# OnOnfre_DevBoard.net
KiCad netlist of a schematic drawn in EAGLE
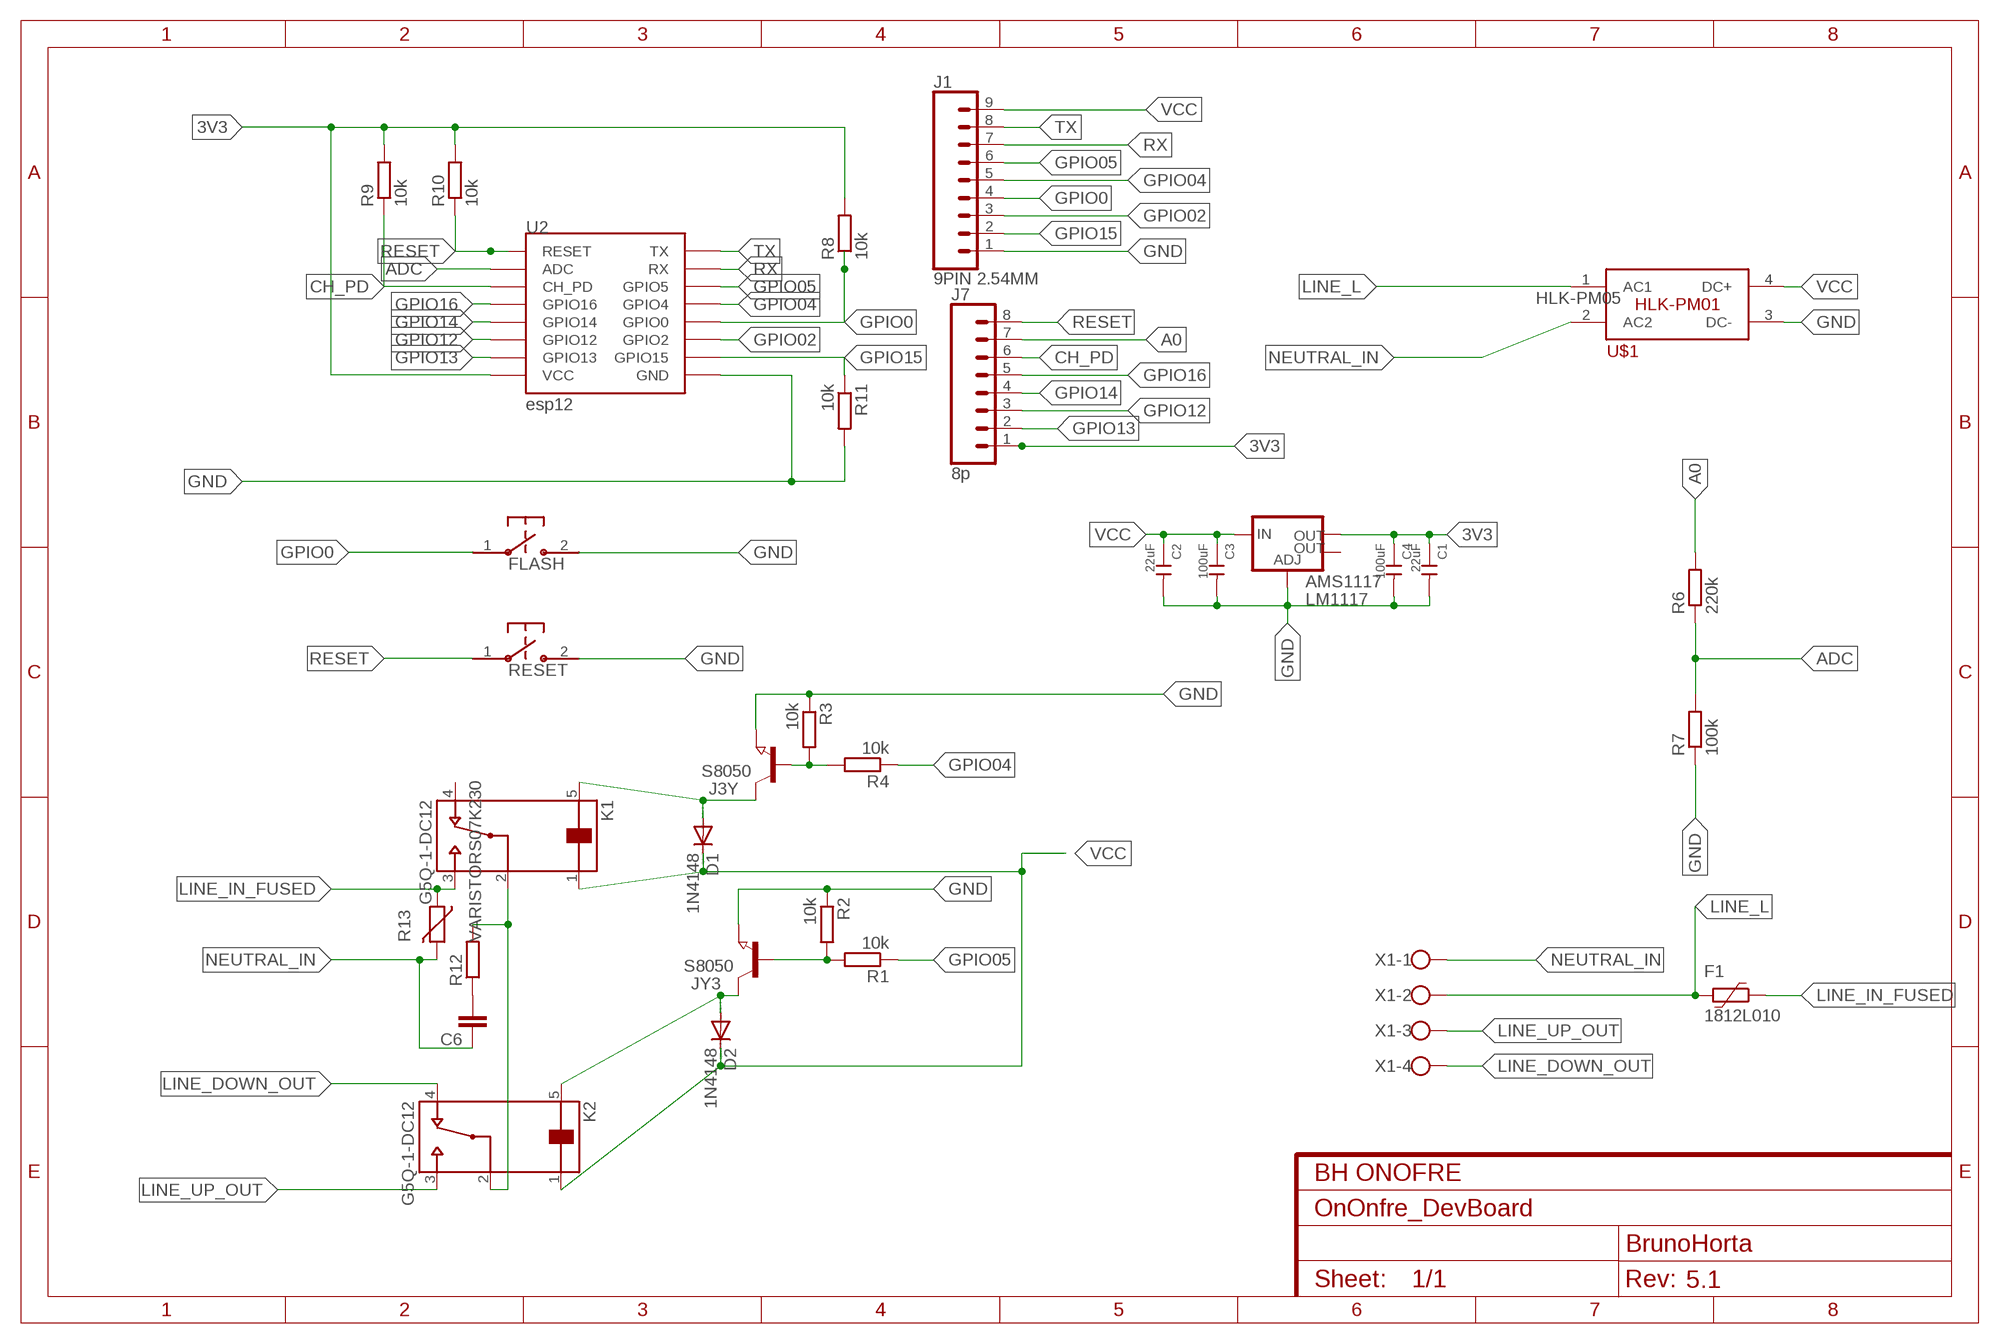
[diagram p0: schematic, sheet 1]

(export (version "E")
  (design (tool "Eeschema 10.0.6"))
  (components
    (comp (ref "AMS1117")
      (value "LM1117")
      (footprint "eagle-import:SOT223")
      (libsource (lib "eagle-import") (part "V_REG_LM1117SOT223"))
    )
    (comp (ref "C1")
      (value "22uF")
      (footprint "eagle-import:C1206")
      (fields (field (name "MPN") "CC1206KKX7RCBB102"))
      (libsource (lib "eagle-import") (part "CERAMIC-1NF-1KV-10%-X7R?(1206)"))
    )
    (comp (ref "C2")
      (value "22uF")
      (footprint "eagle-import:C1206")
      (fields (field (name "MPN") "CC1206KKX7RCBB102"))
      (libsource (lib "eagle-import") (part "CERAMIC-1NF-1KV-10%-X7R?(1206)"))
    )
    (comp (ref "C3")
      (value "100uF")
      (footprint "eagle-import:C1206")
      (fields (field (name "MPN") "CC1206KKX7RCBB102"))
      (libsource (lib "eagle-import") (part "CERAMIC-1NF-1KV-10%-X7R?(1206)"))
    )
    (comp (ref "C4")
      (value "100uF")
      (footprint "eagle-import:C1206")
      (fields (field (name "MPN") "CC1206KKX7RCBB102"))
      (libsource (lib "eagle-import") (part "CERAMIC-1NF-1KV-10%-X7R?(1206)"))
    )
    (comp (ref "C6")
      (value "C-EU102-043X133")
      (footprint "eagle-import:C102-043X133")
      (libsource (lib "eagle-import") (part "C-EU102-043X133"))
    )
    (comp (ref "D1")
      (value "1N4148")
      (footprint "eagle-import:SOD80C")
      (libsource (lib "eagle-import") (part "DIODE-SOD80C"))
    )
    (comp (ref "D2")
      (value "1N4148")
      (footprint "eagle-import:SOD80C")
      (libsource (lib "eagle-import") (part "DIODE-SOD80C"))
    )
    (comp (ref "F1")
      (value "1812L010")
      (footprint "eagle-import:1812L")
      (fields (field (name "MF") "Littelfuse"))
      (libsource (lib "eagle-import") (part "?1812L010"))
    )
    (comp (ref "FLASH")
      (value "B3U-1000P-2P-SMD")
      (footprint "eagle-import:B3U-1000P")
      (fields (field (name "MANUFACTURER") "Omron") (field (name "MPN") "B3U-1000P"))
      (libsource (lib "eagle-import") (part "B3U-1000P"))
    )
    (comp (ref "J1")
      (value "9PIN 2.54MM")
      (footprint "eagle-import:1X09")
      (libsource (lib "eagle-import") (part "CONN_09"))
    )
    (comp (ref "J3Y")
      (value "S8050")
      (footprint "eagle-import:SOT23")
      (libsource (lib "eagle-import") (part "NPN-TRANSISTOR_SOT23"))
    )
    (comp (ref "J7")
      (value "8p")
      (footprint "eagle-import:1X08")
      (libsource (lib "eagle-import") (part "CONN_08{dblquote}"))
    )
    (comp (ref "JY3")
      (value "S8050")
      (footprint "eagle-import:SOT23")
      (libsource (lib "eagle-import") (part "NPN-TRANSISTOR_SOT23"))
    )
    (comp (ref "K1")
      (value "G5Q-1-DC12")
      (footprint "eagle-import:RELAY_G5Q-1-DC12")
      (fields (field (name "MF") "Omron"))
      (libsource (lib "eagle-import") (part "G5Q-1-DC12"))
    )
    (comp (ref "K2")
      (value "G5Q-1-DC12")
      (footprint "eagle-import:RELAY_G5Q-1-DC12")
      (fields (field (name "MF") "Omron"))
      (libsource (lib "eagle-import") (part "G5Q-1-DC12"))
    )
    (comp (ref "R1")
      (value "10k")
      (footprint "eagle-import:R0603")
      (libsource (lib "eagle-import") (part "R-EU_R0603"))
    )
    (comp (ref "R2")
      (value "10k")
      (footprint "eagle-import:R0603")
      (libsource (lib "eagle-import") (part "R-EU_R0603"))
    )
    (comp (ref "R3")
      (value "10k")
      (footprint "eagle-import:R0603")
      (libsource (lib "eagle-import") (part "R-EU_R0603"))
    )
    (comp (ref "R4")
      (value "10k")
      (footprint "eagle-import:R0603")
      (libsource (lib "eagle-import") (part "R-EU_R0603"))
    )
    (comp (ref "R6")
      (value "220k")
      (footprint "eagle-import:R0603")
      (libsource (lib "eagle-import") (part "R-EU_R0603"))
    )
    (comp (ref "R7")
      (value "100k")
      (footprint "eagle-import:R0603")
      (libsource (lib "eagle-import") (part "R-EU_R0603"))
    )
    (comp (ref "R8")
      (value "10k")
      (footprint "eagle-import:R0603")
      (libsource (lib "eagle-import") (part "R-EU_R0603"))
    )
    (comp (ref "R9")
      (value "10k")
      (footprint "eagle-import:R0603")
      (libsource (lib "eagle-import") (part "R-EU_R0603"))
    )
    (comp (ref "R10")
      (value "10k")
      (footprint "eagle-import:R0603")
      (libsource (lib "eagle-import") (part "R-EU_R0603"))
    )
    (comp (ref "R11")
      (value "10k")
      (footprint "eagle-import:R0603")
      (libsource (lib "eagle-import") (part "R-EU_R0603"))
    )
    (comp (ref "R12")
      (value "R-EU_R2512")
      (footprint "eagle-import:R2512")
      (libsource (lib "eagle-import") (part "R-EU_R2512"))
    )
    (comp (ref "R13")
      (value "VARISTORS07K230")
      (footprint "eagle-import:S07K230")
      (libsource (lib "eagle-import") (part "VARISTORS07K230"))
    )
    (comp (ref "RESET")
      (value "B3U-1000P-2P-SMD")
      (footprint "eagle-import:B3U-1000P")
      (fields (field (name "MANUFACTURER") "Omron") (field (name "MPN") "B3U-1000P"))
      (libsource (lib "eagle-import") (part "B3U-1000P"))
    )
    (comp (ref "U$1")
      (value "HLK-PM01")
      (footprint "eagle-import:HLK-PM01")
      (fields (field (name "MF") "Hi-link") (field (name "MP") "hlk-pm01"))
      (libsource (lib "eagle-import") (part "HLK-PM01"))
    )
    (comp (ref "U2")
      (value "esp12")
      (footprint "eagle-import:ESP12-SMD")
      (libsource (lib "eagle-import") (part "ESP12SMD"))
    )
    (comp (ref "X1")
      (value "W237-4")
      (footprint "eagle-import:W237-4")
      (libsource (lib "eagle-import") (part "W237-4"))
    )
  )
  (nets
    (net (code "1") (name "3V3") (class "Default")
      (node (ref "AMS1117") (pin "2") (pinfunction "OUT_2") (pintype "output"))
      (node (ref "C1") (pin "1") (pinfunction "1_1") (pintype "passive"))
      (node (ref "C4") (pin "1") (pinfunction "1_1") (pintype "passive"))
      (node (ref "J7") (pin "1") (pinfunction "1_1") (pintype "passive"))
      (node (ref "R10") (pin "2") (pinfunction "2_2") (pintype "passive"))
      (node (ref "R8") (pin "2") (pinfunction "2_2") (pintype "passive"))
      (node (ref "R9") (pin "2") (pinfunction "2_2") (pintype "passive"))
      (node (ref "U2") (pin "VCC") (pinfunction "VCC_VCC") (pintype "bidirectional"))
    )
    (net (code "2") (name "A0") (class "Default")
      (node (ref "J7") (pin "7") (pinfunction "7_7") (pintype "passive"))
      (node (ref "R6") (pin "2") (pinfunction "2_2") (pintype "passive"))
    )
    (net (code "3") (name "ADC") (class "Default")
      (node (ref "R6") (pin "1") (pinfunction "1_1") (pintype "passive"))
      (node (ref "R7") (pin "2") (pinfunction "2_2") (pintype "passive"))
      (node (ref "U2") (pin "ADC") (pinfunction "ADC_ADC") (pintype "bidirectional"))
    )
    (net (code "4") (name "CH_PD") (class "Default")
      (node (ref "J7") (pin "6") (pinfunction "6_6") (pintype "passive"))
      (node (ref "R9") (pin "1") (pinfunction "1_1") (pintype "passive"))
      (node (ref "U2") (pin "CH_PD") (pinfunction "CH_PD_CH_PD") (pintype "bidirectional"))
    )
    (net (code "5") (name "GND") (class "Default")
      (node (ref "AMS1117") (pin "1") (pinfunction "ADJ_1") (pintype "input"))
      (node (ref "C1") (pin "2") (pinfunction "2_2") (pintype "passive"))
      (node (ref "C2") (pin "2") (pinfunction "2_2") (pintype "passive"))
      (node (ref "C3") (pin "2") (pinfunction "2_2") (pintype "passive"))
      (node (ref "C4") (pin "2") (pinfunction "2_2") (pintype "passive"))
      (node (ref "FLASH") (pin "2") (pinfunction "P$2_2") (pintype "passive"))
      (node (ref "J1") (pin "1") (pinfunction "1_1") (pintype "passive"))
      (node (ref "J3Y") (pin "2") (pinfunction "E_2") (pintype "passive"))
      (node (ref "JY3") (pin "2") (pinfunction "E_2") (pintype "passive"))
      (node (ref "R11") (pin "2") (pinfunction "2_2") (pintype "passive"))
      (node (ref "R2") (pin "1") (pinfunction "1_1") (pintype "passive"))
      (node (ref "R3") (pin "1") (pinfunction "1_1") (pintype "passive"))
      (node (ref "R7") (pin "1") (pinfunction "1_1") (pintype "passive"))
      (node (ref "RESET") (pin "2") (pinfunction "P$2_2") (pintype "passive"))
      (node (ref "U$1") (pin "3") (pinfunction "DC-_3") (pintype "power_in"))
      (node (ref "U2") (pin "GND") (pinfunction "GND_GND") (pintype "bidirectional"))
    )
    (net (code "6") (name "GPIO0") (class "Default")
      (node (ref "FLASH") (pin "1") (pinfunction "P$1_1") (pintype "passive"))
      (node (ref "J1") (pin "4") (pinfunction "4_4") (pintype "passive"))
      (node (ref "R8") (pin "1") (pinfunction "1_1") (pintype "passive"))
      (node (ref "U2") (pin "GPIO0") (pinfunction "GPIO0_GPIO0") (pintype "bidirectional"))
    )
    (net (code "7") (name "GPIO02") (class "Default")
      (node (ref "J1") (pin "3") (pinfunction "3_3") (pintype "passive"))
      (node (ref "U2") (pin "GPIO2") (pinfunction "GPIO2_GPIO2") (pintype "bidirectional"))
    )
    (net (code "8") (name "GPIO04") (class "Default")
      (node (ref "J1") (pin "5") (pinfunction "5_5") (pintype "passive"))
      (node (ref "R4") (pin "1") (pinfunction "1_1") (pintype "passive"))
      (node (ref "U2") (pin "GPIO4") (pinfunction "GPIO4_GPIO4") (pintype "bidirectional"))
    )
    (net (code "9") (name "GPIO05") (class "Default")
      (node (ref "J1") (pin "6") (pinfunction "6_6") (pintype "passive"))
      (node (ref "R1") (pin "1") (pinfunction "1_1") (pintype "passive"))
      (node (ref "U2") (pin "GPIO5") (pinfunction "GPIO5_GPIO5") (pintype "bidirectional"))
    )
    (net (code "10") (name "GPIO12") (class "Default")
      (node (ref "J7") (pin "3") (pinfunction "3_3") (pintype "passive"))
      (node (ref "U2") (pin "GPIO12") (pinfunction "GPIO12_GPIO12") (pintype "bidirectional"))
    )
    (net (code "11") (name "GPIO13") (class "Default")
      (node (ref "J7") (pin "2") (pinfunction "2_2") (pintype "passive"))
      (node (ref "U2") (pin "GPIO13") (pinfunction "GPIO13_GPIO13") (pintype "bidirectional"))
    )
    (net (code "12") (name "GPIO14") (class "Default")
      (node (ref "J7") (pin "4") (pinfunction "4_4") (pintype "passive"))
      (node (ref "U2") (pin "GPIO14") (pinfunction "GPIO14_GPIO14") (pintype "bidirectional"))
    )
    (net (code "13") (name "GPIO15") (class "Default")
      (node (ref "J1") (pin "2") (pinfunction "2_2") (pintype "passive"))
      (node (ref "R11") (pin "1") (pinfunction "1_1") (pintype "passive"))
      (node (ref "U2") (pin "GPIO15") (pinfunction "GPIO15_GPIO15") (pintype "bidirectional"))
    )
    (net (code "14") (name "GPIO16") (class "Default")
      (node (ref "J7") (pin "5") (pinfunction "5_5") (pintype "passive"))
      (node (ref "U2") (pin "GPIO16") (pinfunction "GPIO16_GPIO16") (pintype "bidirectional"))
    )
    (net (code "15") (name "LINE_DOWN_OUT") (class "Default")
      (node (ref "K2") (pin "4") (pinfunction "4_4") (pintype "passive"))
      (node (ref "X1") (pin "4") (pinfunction "KL_4") (pintype "passive"))
    )
    (net (code "16") (name "LINE_IN_FUSED") (class "Default")
      (node (ref "F1") (pin "1") (pinfunction "1_1") (pintype "passive"))
      (node (ref "K1") (pin "3") (pinfunction "3_3") (pintype "passive"))
      (node (ref "R13") (pin "1") (pinfunction "1_1") (pintype "passive"))
    )
    (net (code "17") (name "LINE_L") (class "Default")
      (node (ref "F1") (pin "2") (pinfunction "2_2") (pintype "passive"))
      (node (ref "U$1") (pin "1") (pinfunction "AC1_1") (pintype "power_in"))
      (node (ref "X1") (pin "2") (pinfunction "KL_2") (pintype "passive"))
    )
    (net (code "18") (name "LINE_UP_OUT") (class "Default")
      (node (ref "K2") (pin "3") (pinfunction "3_3") (pintype "passive"))
      (node (ref "X1") (pin "3") (pinfunction "KL_3") (pintype "passive"))
    )
    (net (code "19") (name "NEUTRAL_IN") (class "Default")
      (node (ref "C6") (pin "1") (pinfunction "1_1") (pintype "passive"))
      (node (ref "R13") (pin "2") (pinfunction "2_2") (pintype "passive"))
      (node (ref "U$1") (pin "2") (pinfunction "AC2_2") (pintype "power_in"))
      (node (ref "X1") (pin "1") (pinfunction "KL_1") (pintype "passive"))
    )
    (net (code "20") (name "Net-(C6-Pad2)") (class "Default")
      (node (ref "C6") (pin "2") (pinfunction "2_2") (pintype "passive"))
      (node (ref "R12") (pin "1") (pinfunction "1_1") (pintype "passive"))
    )
    (net (code "21") (name "Net-(J3Y-B)") (class "Default")
      (node (ref "J3Y") (pin "1") (pinfunction "B_1") (pintype "passive"))
      (node (ref "R3") (pin "2") (pinfunction "2_2") (pintype "passive"))
      (node (ref "R4") (pin "2") (pinfunction "2_2") (pintype "passive"))
    )
    (net (code "22") (name "Net-(J3Y-C)") (class "Default")
      (node (ref "D1") (pin "A") (pinfunction "A_A") (pintype "passive"))
      (node (ref "J3Y") (pin "3") (pinfunction "C_3") (pintype "passive"))
      (node (ref "K1") (pin "5") (pinfunction "5_5") (pintype "passive"))
    )
    (net (code "23") (name "Net-(JY3-B)") (class "Default")
      (node (ref "JY3") (pin "1") (pinfunction "B_1") (pintype "passive"))
      (node (ref "R1") (pin "2") (pinfunction "2_2") (pintype "passive"))
      (node (ref "R2") (pin "2") (pinfunction "2_2") (pintype "passive"))
    )
    (net (code "24") (name "Net-(JY3-C)") (class "Default")
      (node (ref "D2") (pin "A") (pinfunction "A_A") (pintype "passive"))
      (node (ref "JY3") (pin "3") (pinfunction "C_3") (pintype "passive"))
      (node (ref "K2") (pin "5") (pinfunction "5_5") (pintype "passive"))
    )
    (net (code "25") (name "Net-(K1-Pad2)") (class "Default")
      (node (ref "K1") (pin "2") (pinfunction "2_2") (pintype "passive"))
      (node (ref "K2") (pin "2") (pinfunction "2_2") (pintype "passive"))
      (node (ref "R12") (pin "2") (pinfunction "2_2") (pintype "passive"))
    )
    (net (code "26") (name "RESET") (class "Default")
      (node (ref "J7") (pin "8") (pinfunction "8_8") (pintype "passive"))
      (node (ref "R10") (pin "1") (pinfunction "1_1") (pintype "passive"))
      (node (ref "RESET") (pin "1") (pinfunction "P$1_1") (pintype "passive"))
      (node (ref "U2") (pin "RESET") (pinfunction "RESET_RESET") (pintype "bidirectional"))
    )
    (net (code "27") (name "RX") (class "Default")
      (node (ref "J1") (pin "7") (pinfunction "7_7") (pintype "passive"))
      (node (ref "U2") (pin "RXD0") (pinfunction "RX_RXD0") (pintype "bidirectional"))
    )
    (net (code "28") (name "TX") (class "Default")
      (node (ref "J1") (pin "8") (pinfunction "8_8") (pintype "passive"))
      (node (ref "U2") (pin "TXD0") (pinfunction "TX_TXD0") (pintype "bidirectional"))
    )
    (net (code "29") (name "VCC") (class "Default")
      (node (ref "AMS1117") (pin "3") (pinfunction "IN_3") (pintype "input"))
      (node (ref "C2") (pin "1") (pinfunction "1_1") (pintype "passive"))
      (node (ref "C3") (pin "1") (pinfunction "1_1") (pintype "passive"))
      (node (ref "D1") (pin "C") (pinfunction "C_C") (pintype "passive"))
      (node (ref "D2") (pin "C") (pinfunction "C_C") (pintype "passive"))
      (node (ref "J1") (pin "9") (pinfunction "9_9") (pintype "passive"))
      (node (ref "K1") (pin "1") (pinfunction "1_1") (pintype "passive"))
      (node (ref "K2") (pin "1") (pinfunction "1_1") (pintype "passive"))
      (node (ref "U$1") (pin "4") (pinfunction "DC+_4") (pintype "power_in"))
    )
    (net (code "30") (name "unconnected-(AMS1117-OUT-Pad4)") (class "Default")
      (node (ref "AMS1117") (pin "4") (pinfunction "OUT_4") (pintype "output"))
    )
    (net (code "31") (name "unconnected-(K1-Pad4)") (class "Default")
      (node (ref "K1") (pin "4") (pinfunction "4_4") (pintype "passive"))
    )
  )
)
